# SUSTAINA-Core-Board.net
KiCad netlist of a schematic drawn in EAGLE
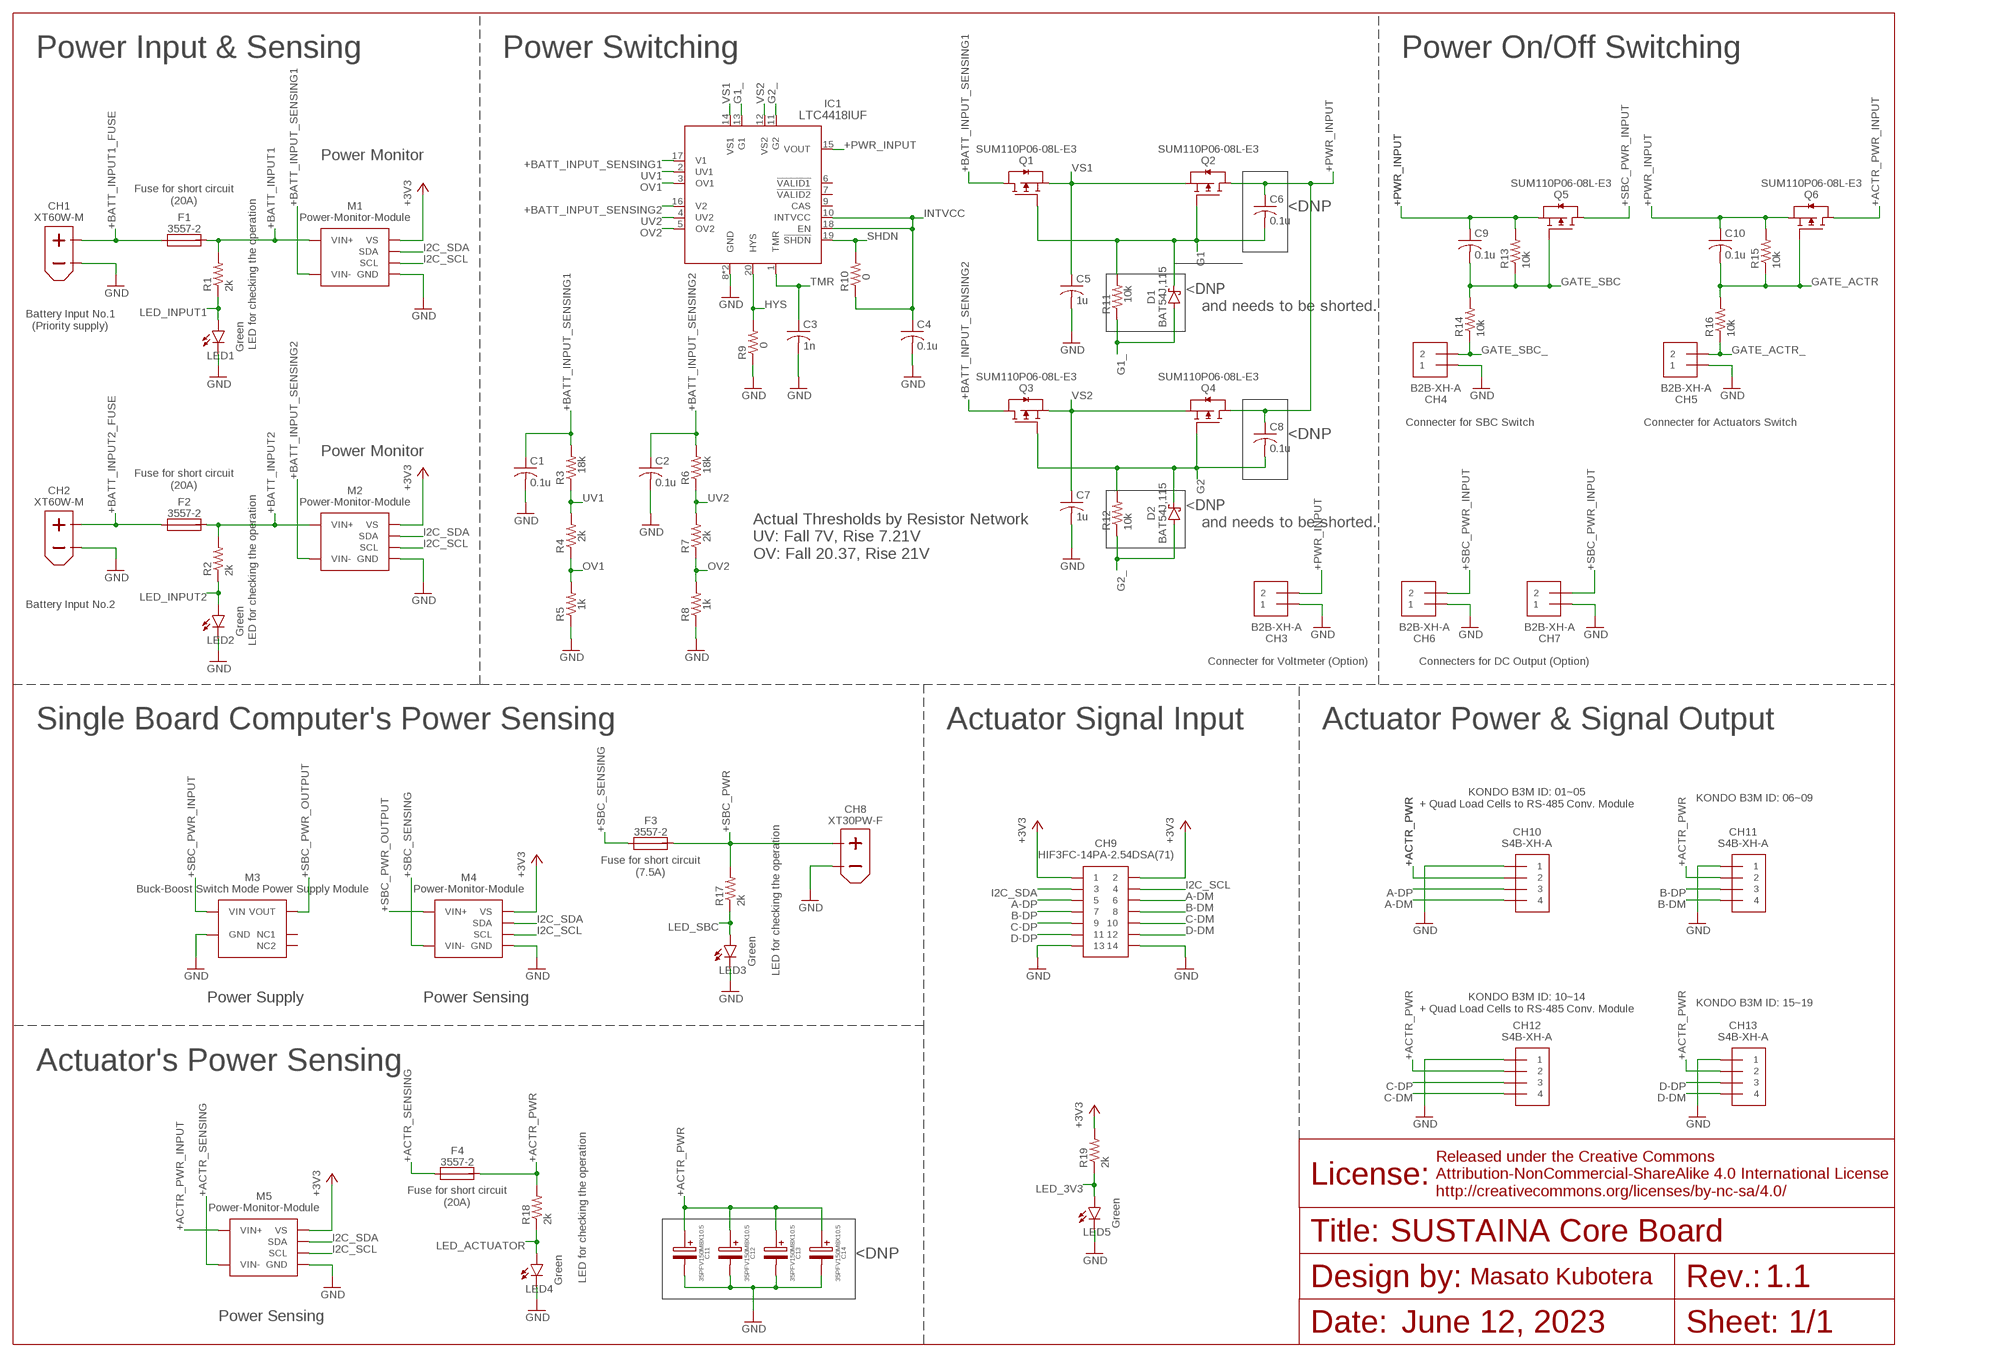
[diagram p0: schematic, sheet 1]

(export (version "E")
  (design (tool "Eeschema 10.0.6"))
  (components
    (comp (ref "C1")
      (value "0.1u")
      (footprint "eagle-import:C0603")
      (libsource (lib "eagle-import") (part "C-USC0603"))
    )
    (comp (ref "C2")
      (value "0.1u")
      (footprint "eagle-import:C0603")
      (libsource (lib "eagle-import") (part "C-USC0603"))
    )
    (comp (ref "C3")
      (value "1n")
      (footprint "eagle-import:C0603")
      (libsource (lib "eagle-import") (part "C-USC0603"))
    )
    (comp (ref "C4")
      (value "0.1u")
      (footprint "eagle-import:C0603")
      (libsource (lib "eagle-import") (part "C-USC0603"))
    )
    (comp (ref "C5")
      (value "1u")
      (footprint "eagle-import:C0603")
      (libsource (lib "eagle-import") (part "C-USC0603"))
    )
    (comp (ref "C6")
      (value "0.1u")
      (footprint "eagle-import:C0603")
      (libsource (lib "eagle-import") (part "C-USC0603"))
    )
    (comp (ref "C7")
      (value "1u")
      (footprint "eagle-import:C0603")
      (libsource (lib "eagle-import") (part "C-USC0603"))
    )
    (comp (ref "C8")
      (value "0.1u")
      (footprint "eagle-import:C0603")
      (libsource (lib "eagle-import") (part "C-USC0603"))
    )
    (comp (ref "C9")
      (value "0.1u")
      (footprint "eagle-import:C0603")
      (libsource (lib "eagle-import") (part "C-USC0603"))
    )
    (comp (ref "C10")
      (value "0.1u")
      (footprint "eagle-import:C0603")
      (libsource (lib "eagle-import") (part "C-USC0603"))
    )
    (comp (ref "C11")
      (value "35PFV150M8X10.5")
      (footprint "eagle-import:35PFV150M8X10.5")
      (libsource (lib "eagle-import") (part "35PFV150M8X10.5"))
    )
    (comp (ref "C12")
      (value "35PFV150M8X10.5")
      (footprint "eagle-import:35PFV150M8X10.5")
      (libsource (lib "eagle-import") (part "35PFV150M8X10.5"))
    )
    (comp (ref "C13")
      (value "35PFV150M8X10.5")
      (footprint "eagle-import:35PFV150M8X10.5")
      (libsource (lib "eagle-import") (part "35PFV150M8X10.5"))
    )
    (comp (ref "C14")
      (value "35PFV150M8X10.5")
      (footprint "eagle-import:35PFV150M8X10.5")
      (libsource (lib "eagle-import") (part "35PFV150M8X10.5"))
    )
    (comp (ref "CH1")
      (value "XT60PW-M")
      (footprint "eagle-import:XT60PW-M")
      (libsource (lib "eagle-import") (part "XT60PW-M"))
    )
    (comp (ref "CH2")
      (value "XT60PW-M")
      (footprint "eagle-import:XT60PW-M")
      (libsource (lib "eagle-import") (part "XT60PW-M"))
    )
    (comp (ref "CH3")
      (value "B2B-XH-A")
      (footprint "eagle-import:B2B-XH-A")
      (libsource (lib "eagle-import") (part "B2B-XH-A"))
    )
    (comp (ref "CH4")
      (value "B2B-XH-A")
      (footprint "eagle-import:B2B-XH-A")
      (libsource (lib "eagle-import") (part "B2B-XH-A"))
    )
    (comp (ref "CH5")
      (value "B2B-XH-A")
      (footprint "eagle-import:B2B-XH-A")
      (libsource (lib "eagle-import") (part "B2B-XH-A"))
    )
    (comp (ref "CH6")
      (value "B2B-XH-A")
      (footprint "eagle-import:B2B-XH-A")
      (libsource (lib "eagle-import") (part "B2B-XH-A"))
    )
    (comp (ref "CH7")
      (value "B2B-XH-A")
      (footprint "eagle-import:B2B-XH-A")
      (libsource (lib "eagle-import") (part "B2B-XH-A"))
    )
    (comp (ref "CH8")
      (value "XT30PW-F")
      (footprint "eagle-import:XT30PW-F")
      (libsource (lib "eagle-import") (part "XT30PW-F"))
    )
    (comp (ref "CH9")
      (value "HIF3FC-14PA-2.54DSA(71)")
      (footprint "eagle-import:HIF3FC-14PA-2.54DSA(71)")
      (libsource (lib "eagle-import") (part "HIF3FC-14PA-2.54DSA(71)"))
    )
    (comp (ref "CH10")
      (value "S4B-XH-A")
      (footprint "eagle-import:S4B-XH-A")
      (libsource (lib "eagle-import") (part "S4B-XH-A"))
    )
    (comp (ref "CH11")
      (value "S4B-XH-A")
      (footprint "eagle-import:S4B-XH-A")
      (libsource (lib "eagle-import") (part "S4B-XH-A"))
    )
    (comp (ref "CH12")
      (value "S4B-XH-A")
      (footprint "eagle-import:S4B-XH-A")
      (libsource (lib "eagle-import") (part "S4B-XH-A"))
    )
    (comp (ref "CH13")
      (value "S4B-XH-A")
      (footprint "eagle-import:S4B-XH-A")
      (libsource (lib "eagle-import") (part "S4B-XH-A"))
    )
    (comp (ref "D1")
      (value "BAT54J,115")
      (footprint "eagle-import:SOD-323-2")
      (libsource (lib "eagle-import") (part "BAT54J,115"))
    )
    (comp (ref "D2")
      (value "BAT54J,115")
      (footprint "eagle-import:SOD-323-2")
      (libsource (lib "eagle-import") (part "BAT54J,115"))
    )
    (comp (ref "F1")
      (value "3557-2")
      (footprint "eagle-import:3557-2")
      (libsource (lib "eagle-import") (part "3557-2"))
    )
    (comp (ref "F2")
      (value "3557-2")
      (footprint "eagle-import:3557-2")
      (libsource (lib "eagle-import") (part "3557-2"))
    )
    (comp (ref "F3")
      (value "3557-2")
      (footprint "eagle-import:3557-2")
      (libsource (lib "eagle-import") (part "3557-2"))
    )
    (comp (ref "F4")
      (value "3557-2")
      (footprint "eagle-import:3557-2")
      (libsource (lib "eagle-import") (part "3557-2"))
    )
    (comp (ref "IC1")
      (value "LTC4418IUF")
      (footprint "eagle-import:LTC4418IUF")
      (libsource (lib "eagle-import") (part "LTC4418IUF"))
    )
    (comp (ref "LED1")
      (value "Green")
      (footprint "eagle-import:SML0603")
      (libsource (lib "eagle-import") (part "LEDSML0603"))
    )
    (comp (ref "LED2")
      (value "Green")
      (footprint "eagle-import:SML0603")
      (libsource (lib "eagle-import") (part "LEDSML0603"))
    )
    (comp (ref "LED3")
      (value "Green")
      (footprint "eagle-import:SML0603")
      (libsource (lib "eagle-import") (part "LEDSML0603"))
    )
    (comp (ref "LED4")
      (value "Green")
      (footprint "eagle-import:SML0603")
      (libsource (lib "eagle-import") (part "LEDSML0603"))
    )
    (comp (ref "LED5")
      (value "Green")
      (footprint "eagle-import:SML0603")
      (libsource (lib "eagle-import") (part "LEDSML0603"))
    )
    (comp (ref "M1")
      (value "POWER-MONITOR-MODULE")
      (footprint "eagle-import:POWER-MONITOR-MODULE")
      (libsource (lib "eagle-import") (part "POWER-MONITOR-MODULE"))
    )
    (comp (ref "M2")
      (value "POWER-MONITOR-MODULE")
      (footprint "eagle-import:POWER-MONITOR-MODULE")
      (libsource (lib "eagle-import") (part "POWER-MONITOR-MODULE"))
    )
    (comp (ref "M3")
      (value "BUCK-BOOST-SWITCH-MODE-POWER-SUPPLY-MODULE")
      (footprint "eagle-import:BUCK-BOOST-SWITCH-MODE-POWER-SUPPLY-MODULE")
      (libsource (lib "eagle-import") (part "BUCK-BOOST-SWITCH-MODE-POWER-SUPPLY-MODULE"))
    )
    (comp (ref "M4")
      (value "POWER-MONITOR-MODULE")
      (footprint "eagle-import:POWER-MONITOR-MODULE")
      (libsource (lib "eagle-import") (part "POWER-MONITOR-MODULE"))
    )
    (comp (ref "M5")
      (value "POWER-MONITOR-MODULE")
      (footprint "eagle-import:POWER-MONITOR-MODULE")
      (libsource (lib "eagle-import") (part "POWER-MONITOR-MODULE"))
    )
    (comp (ref "Q1")
      (value "SUM110P06-08L-E3")
      (footprint "eagle-import:TO-252-3")
      (libsource (lib "eagle-import") (part "SUM110P06-08L-E3"))
    )
    (comp (ref "Q2")
      (value "SUM110P06-08L-E3")
      (footprint "eagle-import:TO-252-3")
      (libsource (lib "eagle-import") (part "SUM110P06-08L-E3"))
    )
    (comp (ref "Q3")
      (value "SUM110P06-08L-E3")
      (footprint "eagle-import:TO-252-3")
      (libsource (lib "eagle-import") (part "SUM110P06-08L-E3"))
    )
    (comp (ref "Q4")
      (value "SUM110P06-08L-E3")
      (footprint "eagle-import:TO-252-3")
      (libsource (lib "eagle-import") (part "SUM110P06-08L-E3"))
    )
    (comp (ref "Q5")
      (value "SUM110P06-08L-E3")
      (footprint "eagle-import:TO-252-3")
      (libsource (lib "eagle-import") (part "SUM110P06-08L-E3"))
    )
    (comp (ref "Q6")
      (value "SUM110P06-08L-E3")
      (footprint "eagle-import:TO-252-3")
      (libsource (lib "eagle-import") (part "SUM110P06-08L-E3"))
    )
    (comp (ref "R1")
      (value "2k")
      (footprint "eagle-import:R0603")
      (libsource (lib "eagle-import") (part "R-US_R0603"))
    )
    (comp (ref "R2")
      (value "2k")
      (footprint "eagle-import:R0603")
      (libsource (lib "eagle-import") (part "R-US_R0603"))
    )
    (comp (ref "R3")
      (value "18k")
      (footprint "eagle-import:R0603")
      (libsource (lib "eagle-import") (part "R-US_R0603"))
    )
    (comp (ref "R4")
      (value "2k")
      (footprint "eagle-import:R0603")
      (libsource (lib "eagle-import") (part "R-US_R0603"))
    )
    (comp (ref "R5")
      (value "1k")
      (footprint "eagle-import:R0603")
      (libsource (lib "eagle-import") (part "R-US_R0603"))
    )
    (comp (ref "R6")
      (value "18k")
      (footprint "eagle-import:R0603")
      (libsource (lib "eagle-import") (part "R-US_R0603"))
    )
    (comp (ref "R7")
      (value "2k")
      (footprint "eagle-import:R0603")
      (libsource (lib "eagle-import") (part "R-US_R0603"))
    )
    (comp (ref "R8")
      (value "1k")
      (footprint "eagle-import:R0603")
      (libsource (lib "eagle-import") (part "R-US_R0603"))
    )
    (comp (ref "R9")
      (value "0")
      (footprint "eagle-import:R0603")
      (libsource (lib "eagle-import") (part "R-US_R0603"))
    )
    (comp (ref "R10")
      (value "0")
      (footprint "eagle-import:R0603")
      (libsource (lib "eagle-import") (part "R-US_R0603"))
    )
    (comp (ref "R11")
      (value "10k")
      (footprint "eagle-import:R0603")
      (libsource (lib "eagle-import") (part "R-US_R0603"))
    )
    (comp (ref "R12")
      (value "10k")
      (footprint "eagle-import:R0603")
      (libsource (lib "eagle-import") (part "R-US_R0603"))
    )
    (comp (ref "R13")
      (value "10k")
      (footprint "eagle-import:R0603")
      (libsource (lib "eagle-import") (part "R-US_R0603"))
    )
    (comp (ref "R14")
      (value "10k")
      (footprint "eagle-import:R0603")
      (libsource (lib "eagle-import") (part "R-US_R0603"))
    )
    (comp (ref "R15")
      (value "10k")
      (footprint "eagle-import:R0603")
      (libsource (lib "eagle-import") (part "R-US_R0603"))
    )
    (comp (ref "R16")
      (value "10k")
      (footprint "eagle-import:R0603")
      (libsource (lib "eagle-import") (part "R-US_R0603"))
    )
    (comp (ref "R17")
      (value "2k")
      (footprint "eagle-import:R0603")
      (libsource (lib "eagle-import") (part "R-US_R0603"))
    )
    (comp (ref "R18")
      (value "2k")
      (footprint "eagle-import:R0603")
      (libsource (lib "eagle-import") (part "R-US_R0603"))
    )
    (comp (ref "R19")
      (value "2k")
      (footprint "eagle-import:R0603")
      (libsource (lib "eagle-import") (part "R-US_R0603"))
    )
  )
  (nets
    (net (code "1") (name "+3V3") (class "Default")
      (node (ref "CH9") (pin "1") (pinfunction "1_1") (pintype "bidirectional"))
      (node (ref "CH9") (pin "2") (pinfunction "2_2") (pintype "bidirectional"))
      (node (ref "M1") (pin "VS") (pinfunction "VS_VS") (pintype "power_in"))
      (node (ref "M2") (pin "VS") (pinfunction "VS_VS") (pintype "power_in"))
      (node (ref "M4") (pin "VS") (pinfunction "VS_VS") (pintype "power_in"))
      (node (ref "M5") (pin "VS") (pinfunction "VS_VS") (pintype "power_in"))
      (node (ref "R19") (pin "2") (pinfunction "2_2") (pintype "passive"))
    )
    (net (code "2") (name "/+ACTR_PWR") (class "Default")
      (node (ref "C11") (pin "+") (pinfunction "+_+") (pintype "bidirectional"))
      (node (ref "C12") (pin "+") (pinfunction "+_+") (pintype "bidirectional"))
      (node (ref "C13") (pin "+") (pinfunction "+_+") (pintype "bidirectional"))
      (node (ref "C14") (pin "+") (pinfunction "+_+") (pintype "bidirectional"))
      (node (ref "CH10") (pin "2") (pinfunction "2_2") (pintype "bidirectional"))
      (node (ref "CH11") (pin "2") (pinfunction "2_2") (pintype "bidirectional"))
      (node (ref "CH12") (pin "2") (pinfunction "2_2") (pintype "bidirectional"))
      (node (ref "CH13") (pin "2") (pinfunction "2_2") (pintype "bidirectional"))
      (node (ref "F4") (pin "3") (pinfunction "2_3") (pintype "bidirectional"))
      (node (ref "F4") (pin "4") (pinfunction "2_4") (pintype "bidirectional"))
      (node (ref "R18") (pin "2") (pinfunction "2_2") (pintype "passive"))
    )
    (net (code "3") (name "/+ACTR_PWR_INPUT") (class "Default")
      (node (ref "M5") (pin "VIN+1") (pinfunction "VIN+_VIN+1") (pintype "power_in"))
      (node (ref "M5") (pin "VIN+10") (pinfunction "VIN+_VIN+10") (pintype "power_in"))
      (node (ref "M5") (pin "VIN+2") (pinfunction "VIN+_VIN+2") (pintype "power_in"))
      (node (ref "M5") (pin "VIN+3") (pinfunction "VIN+_VIN+3") (pintype "power_in"))
      (node (ref "M5") (pin "VIN+4") (pinfunction "VIN+_VIN+4") (pintype "power_in"))
      (node (ref "M5") (pin "VIN+5") (pinfunction "VIN+_VIN+5") (pintype "power_in"))
      (node (ref "M5") (pin "VIN+6") (pinfunction "VIN+_VIN+6") (pintype "power_in"))
      (node (ref "M5") (pin "VIN+7") (pinfunction "VIN+_VIN+7") (pintype "power_in"))
      (node (ref "M5") (pin "VIN+8") (pinfunction "VIN+_VIN+8") (pintype "power_in"))
      (node (ref "M5") (pin "VIN+9") (pinfunction "VIN+_VIN+9") (pintype "power_in"))
      (node (ref "Q6") (pin "4") (pinfunction "D_4") (pintype "bidirectional"))
    )
    (net (code "4") (name "/+ACTR_SENSING") (class "Default")
      (node (ref "F4") (pin "1") (pinfunction "1_1") (pintype "bidirectional"))
      (node (ref "F4") (pin "2") (pinfunction "1_2") (pintype "bidirectional"))
      (node (ref "M5") (pin "VIN-1") (pinfunction "VIN-_VIN-1") (pintype "power_in"))
      (node (ref "M5") (pin "VIN-10") (pinfunction "VIN-_VIN-10") (pintype "power_in"))
      (node (ref "M5") (pin "VIN-2") (pinfunction "VIN-_VIN-2") (pintype "power_in"))
      (node (ref "M5") (pin "VIN-3") (pinfunction "VIN-_VIN-3") (pintype "power_in"))
      (node (ref "M5") (pin "VIN-4") (pinfunction "VIN-_VIN-4") (pintype "power_in"))
      (node (ref "M5") (pin "VIN-5") (pinfunction "VIN-_VIN-5") (pintype "power_in"))
      (node (ref "M5") (pin "VIN-6") (pinfunction "VIN-_VIN-6") (pintype "power_in"))
      (node (ref "M5") (pin "VIN-7") (pinfunction "VIN-_VIN-7") (pintype "power_in"))
      (node (ref "M5") (pin "VIN-8") (pinfunction "VIN-_VIN-8") (pintype "power_in"))
      (node (ref "M5") (pin "VIN-9") (pinfunction "VIN-_VIN-9") (pintype "power_in"))
    )
    (net (code "5") (name "/+BATT_INPUT1") (class "Default")
      (node (ref "F1") (pin "3") (pinfunction "2_3") (pintype "bidirectional"))
      (node (ref "F1") (pin "4") (pinfunction "2_4") (pintype "bidirectional"))
      (node (ref "M1") (pin "VIN+1") (pinfunction "VIN+_VIN+1") (pintype "power_in"))
      (node (ref "M1") (pin "VIN+10") (pinfunction "VIN+_VIN+10") (pintype "power_in"))
      (node (ref "M1") (pin "VIN+2") (pinfunction "VIN+_VIN+2") (pintype "power_in"))
      (node (ref "M1") (pin "VIN+3") (pinfunction "VIN+_VIN+3") (pintype "power_in"))
      (node (ref "M1") (pin "VIN+4") (pinfunction "VIN+_VIN+4") (pintype "power_in"))
      (node (ref "M1") (pin "VIN+5") (pinfunction "VIN+_VIN+5") (pintype "power_in"))
      (node (ref "M1") (pin "VIN+6") (pinfunction "VIN+_VIN+6") (pintype "power_in"))
      (node (ref "M1") (pin "VIN+7") (pinfunction "VIN+_VIN+7") (pintype "power_in"))
      (node (ref "M1") (pin "VIN+8") (pinfunction "VIN+_VIN+8") (pintype "power_in"))
      (node (ref "M1") (pin "VIN+9") (pinfunction "VIN+_VIN+9") (pintype "power_in"))
      (node (ref "R1") (pin "2") (pinfunction "2_2") (pintype "passive"))
    )
    (net (code "6") (name "/+BATT_INPUT1_FUSE") (class "Default")
      (node (ref "CH1") (pin "+") (pinfunction "+_+") (pintype "power_in"))
      (node (ref "F1") (pin "1") (pinfunction "1_1") (pintype "bidirectional"))
      (node (ref "F1") (pin "2") (pinfunction "1_2") (pintype "bidirectional"))
    )
    (net (code "7") (name "/+BATT_INPUT2") (class "Default")
      (node (ref "F2") (pin "3") (pinfunction "2_3") (pintype "bidirectional"))
      (node (ref "F2") (pin "4") (pinfunction "2_4") (pintype "bidirectional"))
      (node (ref "M2") (pin "VIN+1") (pinfunction "VIN+_VIN+1") (pintype "power_in"))
      (node (ref "M2") (pin "VIN+10") (pinfunction "VIN+_VIN+10") (pintype "power_in"))
      (node (ref "M2") (pin "VIN+2") (pinfunction "VIN+_VIN+2") (pintype "power_in"))
      (node (ref "M2") (pin "VIN+3") (pinfunction "VIN+_VIN+3") (pintype "power_in"))
      (node (ref "M2") (pin "VIN+4") (pinfunction "VIN+_VIN+4") (pintype "power_in"))
      (node (ref "M2") (pin "VIN+5") (pinfunction "VIN+_VIN+5") (pintype "power_in"))
      (node (ref "M2") (pin "VIN+6") (pinfunction "VIN+_VIN+6") (pintype "power_in"))
      (node (ref "M2") (pin "VIN+7") (pinfunction "VIN+_VIN+7") (pintype "power_in"))
      (node (ref "M2") (pin "VIN+8") (pinfunction "VIN+_VIN+8") (pintype "power_in"))
      (node (ref "M2") (pin "VIN+9") (pinfunction "VIN+_VIN+9") (pintype "power_in"))
      (node (ref "R2") (pin "2") (pinfunction "2_2") (pintype "passive"))
    )
    (net (code "8") (name "/+BATT_INPUT2_FUSE") (class "Default")
      (node (ref "CH2") (pin "+") (pinfunction "+_+") (pintype "power_in"))
      (node (ref "F2") (pin "1") (pinfunction "1_1") (pintype "bidirectional"))
      (node (ref "F2") (pin "2") (pinfunction "1_2") (pintype "bidirectional"))
    )
    (net (code "9") (name "/+BATT_INPUT_SENSING1") (class "Default")
      (node (ref "C1") (pin "1") (pinfunction "1_1") (pintype "passive"))
      (node (ref "IC1") (pin "17") (pinfunction "V1_17") (pintype "bidirectional"))
      (node (ref "M1") (pin "VIN-1") (pinfunction "VIN-_VIN-1") (pintype "power_in"))
      (node (ref "M1") (pin "VIN-10") (pinfunction "VIN-_VIN-10") (pintype "power_in"))
      (node (ref "M1") (pin "VIN-2") (pinfunction "VIN-_VIN-2") (pintype "power_in"))
      (node (ref "M1") (pin "VIN-3") (pinfunction "VIN-_VIN-3") (pintype "power_in"))
      (node (ref "M1") (pin "VIN-4") (pinfunction "VIN-_VIN-4") (pintype "power_in"))
      (node (ref "M1") (pin "VIN-5") (pinfunction "VIN-_VIN-5") (pintype "power_in"))
      (node (ref "M1") (pin "VIN-6") (pinfunction "VIN-_VIN-6") (pintype "power_in"))
      (node (ref "M1") (pin "VIN-7") (pinfunction "VIN-_VIN-7") (pintype "power_in"))
      (node (ref "M1") (pin "VIN-8") (pinfunction "VIN-_VIN-8") (pintype "power_in"))
      (node (ref "M1") (pin "VIN-9") (pinfunction "VIN-_VIN-9") (pintype "power_in"))
      (node (ref "Q1") (pin "4") (pinfunction "D_4") (pintype "bidirectional"))
      (node (ref "R3") (pin "2") (pinfunction "2_2") (pintype "passive"))
    )
    (net (code "10") (name "/+BATT_INPUT_SENSING2") (class "Default")
      (node (ref "C2") (pin "1") (pinfunction "1_1") (pintype "passive"))
      (node (ref "IC1") (pin "16") (pinfunction "V2_16") (pintype "bidirectional"))
      (node (ref "M2") (pin "VIN-1") (pinfunction "VIN-_VIN-1") (pintype "power_in"))
      (node (ref "M2") (pin "VIN-10") (pinfunction "VIN-_VIN-10") (pintype "power_in"))
      (node (ref "M2") (pin "VIN-2") (pinfunction "VIN-_VIN-2") (pintype "power_in"))
      (node (ref "M2") (pin "VIN-3") (pinfunction "VIN-_VIN-3") (pintype "power_in"))
      (node (ref "M2") (pin "VIN-4") (pinfunction "VIN-_VIN-4") (pintype "power_in"))
      (node (ref "M2") (pin "VIN-5") (pinfunction "VIN-_VIN-5") (pintype "power_in"))
      (node (ref "M2") (pin "VIN-6") (pinfunction "VIN-_VIN-6") (pintype "power_in"))
      (node (ref "M2") (pin "VIN-7") (pinfunction "VIN-_VIN-7") (pintype "power_in"))
      (node (ref "M2") (pin "VIN-8") (pinfunction "VIN-_VIN-8") (pintype "power_in"))
      (node (ref "M2") (pin "VIN-9") (pinfunction "VIN-_VIN-9") (pintype "power_in"))
      (node (ref "Q3") (pin "4") (pinfunction "D_4") (pintype "bidirectional"))
      (node (ref "R6") (pin "2") (pinfunction "2_2") (pintype "passive"))
    )
    (net (code "11") (name "/+PWR_INPUT") (class "Default")
      (node (ref "C10") (pin "1") (pinfunction "1_1") (pintype "passive"))
      (node (ref "C6") (pin "1") (pinfunction "1_1") (pintype "passive"))
      (node (ref "C8") (pin "1") (pinfunction "1_1") (pintype "passive"))
      (node (ref "C9") (pin "1") (pinfunction "1_1") (pintype "passive"))
      (node (ref "CH3") (pin "2") (pinfunction "2_2") (pintype "bidirectional"))
      (node (ref "IC1") (pin "15") (pinfunction "VOUT_15") (pintype "bidirectional"))
      (node (ref "Q2") (pin "4") (pinfunction "D_4") (pintype "bidirectional"))
      (node (ref "Q4") (pin "4") (pinfunction "D_4") (pintype "bidirectional"))
      (node (ref "Q5") (pin "3") (pinfunction "S_3") (pintype "bidirectional"))
      (node (ref "Q6") (pin "3") (pinfunction "S_3") (pintype "bidirectional"))
      (node (ref "R13") (pin "2") (pinfunction "2_2") (pintype "passive"))
      (node (ref "R15") (pin "2") (pinfunction "2_2") (pintype "passive"))
    )
    (net (code "12") (name "/+SBC_PWR") (class "Default")
      (node (ref "CH8") (pin "+") (pinfunction "+_+") (pintype "power_in"))
      (node (ref "F3") (pin "3") (pinfunction "2_3") (pintype "bidirectional"))
      (node (ref "F3") (pin "4") (pinfunction "2_4") (pintype "bidirectional"))
      (node (ref "R17") (pin "2") (pinfunction "2_2") (pintype "passive"))
    )
    (net (code "13") (name "/+SBC_PWR_INPUT") (class "Default")
      (node (ref "CH6") (pin "2") (pinfunction "2_2") (pintype "bidirectional"))
      (node (ref "CH7") (pin "2") (pinfunction "2_2") (pintype "bidirectional"))
      (node (ref "M3") (pin "VIN1") (pinfunction "VIN_VIN1") (pintype "bidirectional"))
      (node (ref "M3") (pin "VIN2") (pinfunction "VIN_VIN2") (pintype "bidirectional"))
      (node (ref "M3") (pin "VIN3") (pinfunction "VIN_VIN3") (pintype "bidirectional"))
      (node (ref "Q5") (pin "4") (pinfunction "D_4") (pintype "bidirectional"))
    )
    (net (code "14") (name "/+SBC_PWR_OUTPUT") (class "Default")
      (node (ref "M3") (pin "VOUT1") (pinfunction "VOUT_VOUT1") (pintype "bidirectional"))
      (node (ref "M3") (pin "VOUT2") (pinfunction "VOUT_VOUT2") (pintype "bidirectional"))
      (node (ref "M3") (pin "VOUT3") (pinfunction "VOUT_VOUT3") (pintype "bidirectional"))
      (node (ref "M4") (pin "VIN+1") (pinfunction "VIN+_VIN+1") (pintype "power_in"))
      (node (ref "M4") (pin "VIN+10") (pinfunction "VIN+_VIN+10") (pintype "power_in"))
      (node (ref "M4") (pin "VIN+2") (pinfunction "VIN+_VIN+2") (pintype "power_in"))
      (node (ref "M4") (pin "VIN+3") (pinfunction "VIN+_VIN+3") (pintype "power_in"))
      (node (ref "M4") (pin "VIN+4") (pinfunction "VIN+_VIN+4") (pintype "power_in"))
      (node (ref "M4") (pin "VIN+5") (pinfunction "VIN+_VIN+5") (pintype "power_in"))
      (node (ref "M4") (pin "VIN+6") (pinfunction "VIN+_VIN+6") (pintype "power_in"))
      (node (ref "M4") (pin "VIN+7") (pinfunction "VIN+_VIN+7") (pintype "power_in"))
      (node (ref "M4") (pin "VIN+8") (pinfunction "VIN+_VIN+8") (pintype "power_in"))
      (node (ref "M4") (pin "VIN+9") (pinfunction "VIN+_VIN+9") (pintype "power_in"))
    )
    (net (code "15") (name "/+SBC_SENSING") (class "Default")
      (node (ref "F3") (pin "1") (pinfunction "1_1") (pintype "bidirectional"))
      (node (ref "F3") (pin "2") (pinfunction "1_2") (pintype "bidirectional"))
      (node (ref "M4") (pin "VIN-1") (pinfunction "VIN-_VIN-1") (pintype "power_in"))
      (node (ref "M4") (pin "VIN-10") (pinfunction "VIN-_VIN-10") (pintype "power_in"))
      (node (ref "M4") (pin "VIN-2") (pinfunction "VIN-_VIN-2") (pintype "power_in"))
      (node (ref "M4") (pin "VIN-3") (pinfunction "VIN-_VIN-3") (pintype "power_in"))
      (node (ref "M4") (pin "VIN-4") (pinfunction "VIN-_VIN-4") (pintype "power_in"))
      (node (ref "M4") (pin "VIN-5") (pinfunction "VIN-_VIN-5") (pintype "power_in"))
      (node (ref "M4") (pin "VIN-6") (pinfunction "VIN-_VIN-6") (pintype "power_in"))
      (node (ref "M4") (pin "VIN-7") (pinfunction "VIN-_VIN-7") (pintype "power_in"))
      (node (ref "M4") (pin "VIN-8") (pinfunction "VIN-_VIN-8") (pintype "power_in"))
      (node (ref "M4") (pin "VIN-9") (pinfunction "VIN-_VIN-9") (pintype "power_in"))
    )
    (net (code "16") (name "/A-DM") (class "Default")
      (node (ref "CH10") (pin "4") (pinfunction "4_4") (pintype "bidirectional"))
      (node (ref "CH9") (pin "6") (pinfunction "6_6") (pintype "bidirectional"))
    )
    (net (code "17") (name "/A-DP") (class "Default")
      (node (ref "CH10") (pin "3") (pinfunction "3_3") (pintype "bidirectional"))
      (node (ref "CH9") (pin "5") (pinfunction "5_5") (pintype "bidirectional"))
    )
    (net (code "18") (name "/B-DM") (class "Default")
      (node (ref "CH11") (pin "4") (pinfunction "4_4") (pintype "bidirectional"))
      (node (ref "CH9") (pin "8") (pinfunction "8_8") (pintype "bidirectional"))
    )
    (net (code "19") (name "/B-DP") (class "Default")
      (node (ref "CH11") (pin "3") (pinfunction "3_3") (pintype "bidirectional"))
      (node (ref "CH9") (pin "7") (pinfunction "7_7") (pintype "bidirectional"))
    )
    (net (code "20") (name "/C-DM") (class "Default")
      (node (ref "CH12") (pin "4") (pinfunction "4_4") (pintype "bidirectional"))
      (node (ref "CH9") (pin "10") (pinfunction "10_10") (pintype "bidirectional"))
    )
    (net (code "21") (name "/C-DP") (class "Default")
      (node (ref "CH12") (pin "3") (pinfunction "3_3") (pintype "bidirectional"))
      (node (ref "CH9") (pin "9") (pinfunction "9_9") (pintype "bidirectional"))
    )
    (net (code "22") (name "/D-DM") (class "Default")
      (node (ref "CH13") (pin "4") (pinfunction "4_4") (pintype "bidirectional"))
      (node (ref "CH9") (pin "12") (pinfunction "12_12") (pintype "bidirectional"))
    )
    (net (code "23") (name "/D-DP") (class "Default")
      (node (ref "CH13") (pin "3") (pinfunction "3_3") (pintype "bidirectional"))
      (node (ref "CH9") (pin "11") (pinfunction "11_11") (pintype "bidirectional"))
    )
    (net (code "24") (name "/G1") (class "Default")
      (node (ref "C6") (pin "2") (pinfunction "2_2") (pintype "passive"))
      (node (ref "D1") (pin "1") (pinfunction "C_1") (pintype "passive"))
      (node (ref "Q1") (pin "1") (pinfunction "G_1") (pintype "bidirectional"))
      (node (ref "Q2") (pin "1") (pinfunction "G_1") (pintype "bidirectional"))
      (node (ref "R11") (pin "2") (pinfunction "2_2") (pintype "passive"))
    )
    (net (code "25") (name "/G1_") (class "Default")
      (node (ref "D1") (pin "2") (pinfunction "A_2") (pintype "passive"))
      (node (ref "IC1") (pin "13") (pinfunction "G1_13") (pintype "bidirectional"))
      (node (ref "R11") (pin "1") (pinfunction "1_1") (pintype "passive"))
    )
    (net (code "26") (name "/G2") (class "Default")
      (node (ref "C8") (pin "2") (pinfunction "2_2") (pintype "passive"))
      (node (ref "D2") (pin "1") (pinfunction "C_1") (pintype "passive"))
      (node (ref "Q3") (pin "1") (pinfunction "G_1") (pintype "bidirectional"))
      (node (ref "Q4") (pin "1") (pinfunction "G_1") (pintype "bidirectional"))
      (node (ref "R12") (pin "2") (pinfunction "2_2") (pintype "passive"))
    )
    (net (code "27") (name "/G2_") (class "Default")
      (node (ref "D2") (pin "2") (pinfunction "A_2") (pintype "passive"))
      (node (ref "IC1") (pin "11") (pinfunction "G2_11") (pintype "bidirectional"))
      (node (ref "R12") (pin "1") (pinfunction "1_1") (pintype "passive"))
    )
    (net (code "28") (name "/GATE_ACTR") (class "Default")
      (node (ref "C10") (pin "2") (pinfunction "2_2") (pintype "passive"))
      (node (ref "Q6") (pin "1") (pinfunction "G_1") (pintype "bidirectional"))
      (node (ref "R15") (pin "1") (pinfunction "1_1") (pintype "passive"))
      (node (ref "R16") (pin "2") (pinfunction "2_2") (pintype "passive"))
    )
    (net (code "29") (name "/GATE_ACTR_") (class "Default")
      (node (ref "CH5") (pin "2") (pinfunction "2_2") (pintype "bidirectional"))
      (node (ref "R16") (pin "1") (pinfunction "1_1") (pintype "passive"))
    )
    (net (code "30") (name "/GATE_SBC") (class "Default")
      (node (ref "C9") (pin "2") (pinfunction "2_2") (pintype "passive"))
      (node (ref "Q5") (pin "1") (pinfunction "G_1") (pintype "bidirectional"))
      (node (ref "R13") (pin "1") (pinfunction "1_1") (pintype "passive"))
      (node (ref "R14") (pin "2") (pinfunction "2_2") (pintype "passive"))
    )
    (net (code "31") (name "/GATE_SBC_") (class "Default")
      (node (ref "CH4") (pin "2") (pinfunction "2_2") (pintype "bidirectional"))
      (node (ref "R14") (pin "1") (pinfunction "1_1") (pintype "passive"))
    )
    (net (code "32") (name "/HYS") (class "Default")
      (node (ref "IC1") (pin "20") (pinfunction "HYS_20") (pintype "bidirectional"))
      (node (ref "R9") (pin "2") (pinfunction "2_2") (pintype "passive"))
    )
    (net (code "33") (name "/I2C_SCL") (class "Default")
      (node (ref "CH9") (pin "4") (pinfunction "4_4") (pintype "bidirectional"))
      (node (ref "M1") (pin "SCL") (pinfunction "SCL_SCL") (pintype "bidirectional"))
      (node (ref "M2") (pin "SCL") (pinfunction "SCL_SCL") (pintype "bidirectional"))
      (node (ref "M4") (pin "SCL") (pinfunction "SCL_SCL") (pintype "bidirectional"))
      (node (ref "M5") (pin "SCL") (pinfunction "SCL_SCL") (pintype "bidirectional"))
    )
    (net (code "34") (name "/I2C_SDA") (class "Default")
      (node (ref "CH9") (pin "3") (pinfunction "3_3") (pintype "bidirectional"))
      (node (ref "M1") (pin "SDA") (pinfunction "SDA_SDA") (pintype "bidirectional"))
      (node (ref "M2") (pin "SDA") (pinfunction "SDA_SDA") (pintype "bidirectional"))
      (node (ref "M4") (pin "SDA") (pinfunction "SDA_SDA") (pintype "bidirectional"))
      (node (ref "M5") (pin "SDA") (pinfunction "SDA_SDA") (pintype "bidirectional"))
    )
    (net (code "35") (name "/INTVCC") (class "Default")
      (node (ref "C4") (pin "1") (pinfunction "1_1") (pintype "passive"))
      (node (ref "IC1") (pin "10") (pinfunction "INTVCC_10") (pintype "bidirectional"))
      (node (ref "IC1") (pin "18") (pinfunction "EN_18") (pintype "bidirectional"))
      (node (ref "R10") (pin "1") (pinfunction "1_1") (pintype "passive"))
    )
    (net (code "36") (name "/LED_3V3") (class "Default")
      (node (ref "LED5") (pin "A") (pinfunction "A_A") (pintype "passive"))
      (node (ref "R19") (pin "1") (pinfunction "1_1") (pintype "passive"))
    )
    (net (code "37") (name "/LED_ACTUATOR") (class "Default")
      (node (ref "LED4") (pin "A") (pinfunction "A_A") (pintype "passive"))
      (node (ref "R18") (pin "1") (pinfunction "1_1") (pintype "passive"))
    )
    (net (code "38") (name "/LED_INPUT1") (class "Default")
      (node (ref "LED1") (pin "A") (pinfunction "A_A") (pintype "passive"))
      (node (ref "R1") (pin "1") (pinfunction "1_1") (pintype "passive"))
    )
    (net (code "39") (name "/LED_INPUT2") (class "Default")
      (node (ref "LED2") (pin "A") (pinfunction "A_A") (pintype "passive"))
      (node (ref "R2") (pin "1") (pinfunction "1_1") (pintype "passive"))
    )
    (net (code "40") (name "/LED_SBC") (class "Default")
      (node (ref "LED3") (pin "A") (pinfunction "A_A") (pintype "passive"))
      (node (ref "R17") (pin "1") (pinfunction "1_1") (pintype "passive"))
    )
    (net (code "41") (name "/OV1") (class "Default")
      (node (ref "IC1") (pin "3") (pinfunction "OV1_3") (pintype "bidirectional"))
      (node (ref "R4") (pin "1") (pinfunction "1_1") (pintype "passive"))
      (node (ref "R5") (pin "2") (pinfunction "2_2") (pintype "passive"))
    )
    (net (code "42") (name "/OV2") (class "Default")
      (node (ref "IC1") (pin "5") (pinfunction "OV2_5") (pintype "bidirectional"))
      (node (ref "R7") (pin "1") (pinfunction "1_1") (pintype "passive"))
      (node (ref "R8") (pin "2") (pinfunction "2_2") (pintype "passive"))
    )
    (net (code "43") (name "/SHDN") (class "Default")
      (node (ref "IC1") (pin "19") (pinfunction "~{SHDN}_19") (pintype "bidirectional"))
      (node (ref "R10") (pin "2") (pinfunction "2_2") (pintype "passive"))
    )
    (net (code "44") (name "/TMR") (class "Default")
      (node (ref "C3") (pin "1") (pinfunction "1_1") (pintype "passive"))
      (node (ref "IC1") (pin "1") (pinfunction "TMR_1") (pintype "bidirectional"))
    )
    (net (code "45") (name "/UV1") (class "Default")
      (node (ref "IC1") (pin "2") (pinfunction "UV1_2") (pintype "bidirectional"))
      (node (ref "R3") (pin "1") (pinfunction "1_1") (pintype "passive"))
      (node (ref "R4") (pin "2") (pinfunction "2_2") (pintype "passive"))
    )
    (net (code "46") (name "/UV2") (class "Default")
      (node (ref "IC1") (pin "4") (pinfunction "UV2_4") (pintype "bidirectional"))
      (node (ref "R6") (pin "1") (pinfunction "1_1") (pintype "passive"))
      (node (ref "R7") (pin "2") (pinfunction "2_2") (pintype "passive"))
    )
    (net (code "47") (name "/VS1") (class "Default")
      (node (ref "C5") (pin "1") (pinfunction "1_1") (pintype "passive"))
      (node (ref "IC1") (pin "14") (pinfunction "VS1_14") (pintype "bidirectional"))
      (node (ref "Q1") (pin "3") (pinfunction "S_3") (pintype "bidirectional"))
      (node (ref "Q2") (pin "3") (pinfunction "S_3") (pintype "bidirectional"))
    )
    (net (code "48") (name "/VS2") (class "Default")
      (node (ref "C7") (pin "1") (pinfunction "1_1") (pintype "passive"))
      (node (ref "IC1") (pin "12") (pinfunction "VS2_12") (pintype "bidirectional"))
      (node (ref "Q3") (pin "3") (pinfunction "S_3") (pintype "bidirectional"))
      (node (ref "Q4") (pin "3") (pinfunction "S_3") (pintype "bidirectional"))
    )
    (net (code "49") (name "GND") (class "Default")
      (node (ref "C1") (pin "2") (pinfunction "2_2") (pintype "passive"))
      (node (ref "C11") (pin "-") (pinfunction "-_-") (pintype "bidirectional"))
      (node (ref "C12") (pin "-") (pinfunction "-_-") (pintype "bidirectional"))
      (node (ref "C13") (pin "-") (pinfunction "-_-") (pintype "bidirectional"))
      (node (ref "C14") (pin "-") (pinfunction "-_-") (pintype "bidirectional"))
      (node (ref "C2") (pin "2") (pinfunction "2_2") (pintype "passive"))
      (node (ref "C3") (pin "2") (pinfunction "2_2") (pintype "passive"))
      (node (ref "C4") (pin "2") (pinfunction "2_2") (pintype "passive"))
      (node (ref "C5") (pin "2") (pinfunction "2_2") (pintype "passive"))
      (node (ref "C7") (pin "2") (pinfunction "2_2") (pintype "passive"))
      (node (ref "CH1") (pin "-") (pinfunction "-_-") (pintype "power_in"))
      (node (ref "CH10") (pin "1") (pinfunction "1_1") (pintype "bidirectional"))
      (node (ref "CH11") (pin "1") (pinfunction "1_1") (pintype "bidirectional"))
      (node (ref "CH12") (pin "1") (pinfunction "1_1") (pintype "bidirectional"))
      (node (ref "CH13") (pin "1") (pinfunction "1_1") (pintype "bidirectional"))
      (node (ref "CH2") (pin "-") (pinfunction "-_-") (pintype "power_in"))
      (node (ref "CH3") (pin "1") (pinfunction "1_1") (pintype "bidirectional"))
      (node (ref "CH4") (pin "1") (pinfunction "1_1") (pintype "bidirectional"))
      (node (ref "CH5") (pin "1") (pinfunction "1_1") (pintype "bidirectional"))
      (node (ref "CH6") (pin "1") (pinfunction "1_1") (pintype "bidirectional"))
      (node (ref "CH7") (pin "1") (pinfunction "1_1") (pintype "bidirectional"))
      (node (ref "CH8") (pin "-") (pinfunction "-_-") (pintype "power_in"))
      (node (ref "CH9") (pin "13") (pinfunction "13_13") (pintype "bidirectional"))
      (node (ref "CH9") (pin "14") (pinfunction "14_14") (pintype "bidirectional"))
      (node (ref "IC1") (pin "21") (pinfunction "GND_21") (pintype "bidirectional"))
      (node (ref "IC1") (pin "8") (pinfunction "GND_8") (pintype "bidirectional"))
      (node (ref "LED1") (pin "C") (pinfunction "C_C") (pintype "passive"))
      (node (ref "LED2") (pin "C") (pinfunction "C_C") (pintype "passive"))
      (node (ref "LED3") (pin "C") (pinfunction "C_C") (pintype "passive"))
      (node (ref "LED4") (pin "C") (pinfunction "C_C") (pintype "passive"))
      (node (ref "LED5") (pin "C") (pinfunction "C_C") (pintype "passive"))
      (node (ref "M1") (pin "GND") (pinfunction "GND_GND") (pintype "power_in"))
      (node (ref "M2") (pin "GND") (pinfunction "GND_GND") (pintype "power_in"))
      (node (ref "M3") (pin "GND1") (pinfunction "GND_GND1") (pintype "bidirectional"))
      (node (ref "M3") (pin "GND2") (pinfunction "GND_GND2") (pintype "bidirectional"))
      (node (ref "M3") (pin "GND3") (pinfunction "GND_GND3") (pintype "bidirectional"))
      (node (ref "M3") (pin "GND4") (pinfunction "GND_GND4") (pintype "bidirectional"))
      (node (ref "M3") (pin "GND5") (pinfunction "GND_GND5") (pintype "bidirectional"))
      (node (ref "M3") (pin "GND6") (pinfunction "GND_GND6") (pintype "bidirectional"))
      (node (ref "M4") (pin "GND") (pinfunction "GND_GND") (pintype "power_in"))
      (node (ref "M5") (pin "GND") (pinfunction "GND_GND") (pintype "power_in"))
      (node (ref "R5") (pin "1") (pinfunction "1_1") (pintype "passive"))
      (node (ref "R8") (pin "1") (pinfunction "1_1") (pintype "passive"))
      (node (ref "R9") (pin "1") (pinfunction "1_1") (pintype "passive"))
    )
    (net (code "50") (name "unconnected-(IC1-CAS-Pad9)") (class "Default")
      (node (ref "IC1") (pin "9") (pinfunction "CAS_9") (pintype "bidirectional"))
    )
    (net (code "51") (name "unconnected-(IC1-~{VALID1}-Pad6)") (class "Default")
      (node (ref "IC1") (pin "6") (pinfunction "~{VALID1}_6") (pintype "bidirectional"))
    )
    (net (code "52") (name "unconnected-(IC1-~{VALID2}-Pad7)") (class "Default")
      (node (ref "IC1") (pin "7") (pinfunction "~{VALID2}_7") (pintype "bidirectional"))
    )
    (net (code "53") (name "unconnected-(M3-PadNC1)") (class "Default")
      (node (ref "M3") (pin "NC1") (pinfunction "NC1_NC1") (pintype "no_connect"))
    )
    (net (code "54") (name "unconnected-(M3-PadNC2)") (class "Default")
      (node (ref "M3") (pin "NC2") (pinfunction "NC2_NC2") (pintype "no_connect"))
    )
  )
)
